# avr_101.net
KiCad netlist of a schematic drawn in EAGLE
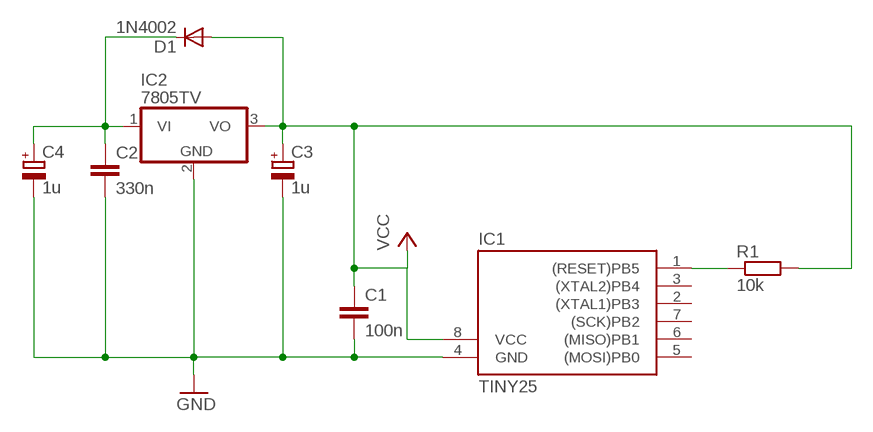
[diagram p0: schematic, sheet 1]

(export (version "E")
  (design (tool "Eeschema 10.0.6"))
  (components
    (comp (ref "C1")
      (value "100n")
      (footprint "eagle-import:C0805")
      (libsource (lib "eagle-import") (part "C-EUC0805"))
    )
    (comp (ref "C2")
      (value "330n")
      (footprint "eagle-import:C0805")
      (libsource (lib "eagle-import") (part "C-EUC0805"))
    )
    (comp (ref "C3")
      (value "1u")
      (footprint "eagle-import:150CLZ-0810")
      (libsource (lib "eagle-import") (part "CPOL-EU150CLZ-0810"))
    )
    (comp (ref "C4")
      (value "1u")
      (footprint "eagle-import:150CLZ-0810")
      (libsource (lib "eagle-import") (part "CPOL-EU150CLZ-0810"))
    )
    (comp (ref "D1")
      (value "1N4002")
      (footprint "eagle-import:DO41-10")
      (libsource (lib "eagle-import") (part "1N4004"))
    )
    (comp (ref "IC1")
      (value "TINY25")
      (footprint "eagle-import:DIL08")
      (libsource (lib "eagle-import") (part "TINY12P"))
    )
    (comp (ref "IC2")
      (value "7805TV")
      (footprint "eagle-import:TO220V")
      (libsource (lib "eagle-import") (part "78TV05"))
    )
    (comp (ref "R1")
      (value "10k")
      (footprint "eagle-import:R0805")
      (libsource (lib "eagle-import") (part "R-EU_R0805"))
    )
  )
  (nets
    (net (code "1") (name "GND") (class "Default")
      (node (ref "C1") (pin "2") (pinfunction "2_2") (pintype "passive"))
      (node (ref "C2") (pin "2") (pinfunction "2_2") (pintype "passive"))
      (node (ref "C3") (pin "-") (pinfunction "-_-") (pintype "passive"))
      (node (ref "C4") (pin "-") (pinfunction "-_-") (pintype "passive"))
      (node (ref "IC1") (pin "4") (pinfunction "GND_4") (pintype "power_in"))
      (node (ref "IC2") (pin "2") (pinfunction "GND_2") (pintype "passive"))
    )
    (net (code "2") (name "Net-(IC1-(RESET)PB5)") (class "Default")
      (node (ref "IC1") (pin "1") (pinfunction "(RESET)PB5_1") (pintype "bidirectional"))
      (node (ref "R1") (pin "1") (pinfunction "1_1") (pintype "passive"))
    )
    (net (code "3") (name "Net-(IC2-VI)") (class "Default")
      (node (ref "C2") (pin "1") (pinfunction "1_1") (pintype "passive"))
      (node (ref "C4") (pin "+") (pinfunction "+_+") (pintype "passive"))
      (node (ref "D1") (pin "C") (pinfunction "C_C") (pintype "passive"))
      (node (ref "IC2") (pin "1") (pinfunction "VI_1") (pintype "input"))
    )
    (net (code "4") (name "VCC") (class "Default")
      (node (ref "C1") (pin "1") (pinfunction "1_1") (pintype "passive"))
      (node (ref "C3") (pin "+") (pinfunction "+_+") (pintype "passive"))
      (node (ref "D1") (pin "A") (pinfunction "A_A") (pintype "passive"))
      (node (ref "IC1") (pin "8") (pinfunction "VCC_8") (pintype "power_in"))
      (node (ref "IC2") (pin "3") (pinfunction "VO_3") (pintype "passive"))
      (node (ref "R1") (pin "2") (pinfunction "2_2") (pintype "passive"))
    )
    (net (code "5") (name "unconnected-(IC1-(MISO)PB1-Pad6)") (class "Default")
      (node (ref "IC1") (pin "6") (pinfunction "(MISO)PB1_6") (pintype "bidirectional"))
    )
    (net (code "6") (name "unconnected-(IC1-(MOSI)PB0-Pad5)") (class "Default")
      (node (ref "IC1") (pin "5") (pinfunction "(MOSI)PB0_5") (pintype "bidirectional"))
    )
    (net (code "7") (name "unconnected-(IC1-(SCK)PB2-Pad7)") (class "Default")
      (node (ref "IC1") (pin "7") (pinfunction "(SCK)PB2_7") (pintype "bidirectional"))
    )
    (net (code "8") (name "unconnected-(IC1-(XTAL1)PB3-Pad2)") (class "Default")
      (node (ref "IC1") (pin "2") (pinfunction "(XTAL1)PB3_2") (pintype "bidirectional"))
    )
    (net (code "9") (name "unconnected-(IC1-(XTAL2)PB4-Pad3)") (class "Default")
      (node (ref "IC1") (pin "3") (pinfunction "(XTAL2)PB4_3") (pintype "bidirectional"))
    )
  )
)
